# VGA.net
KiCad netlist of a schematic drawn in Altium Designer
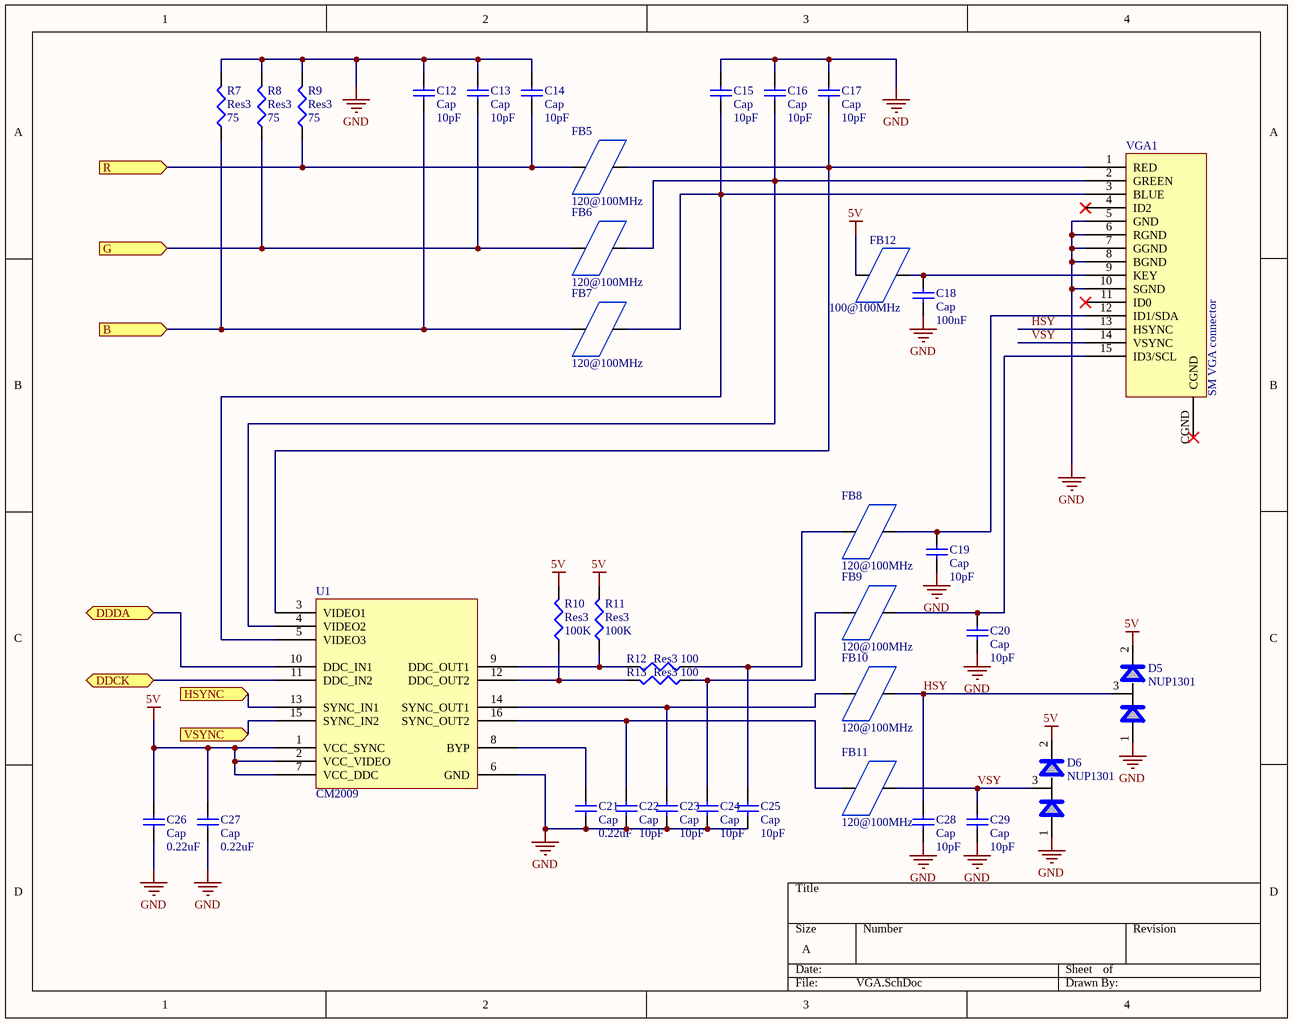
[diagram p0: VGA.SchDoc]

(export (version "E")
  (design (tool "Eeschema 10.0.6"))
  (components
    (comp (ref "C12")
      (value "Cap")
      (footprint "0603")
      (description "Capacitor")
      (fields (field (name "ALTIUM_VALUE") "10pF") (field (name "PUBLISHER") "Altium Limited"))
      (libsource (lib "Miscellaneous Devices") (part "Cap"))
    )
    (comp (ref "C13")
      (value "Cap")
      (footprint "0603")
      (description "Capacitor")
      (fields (field (name "ALTIUM_VALUE") "10pF") (field (name "PUBLISHER") "Altium Limited"))
      (libsource (lib "Miscellaneous Devices") (part "Cap"))
    )
    (comp (ref "C14")
      (value "Cap")
      (footprint "0603")
      (description "Capacitor")
      (fields (field (name "ALTIUM_VALUE") "10pF") (field (name "PUBLISHER") "Altium Limited"))
      (libsource (lib "Miscellaneous Devices") (part "Cap"))
    )
    (comp (ref "C15")
      (value "Cap")
      (footprint "0603")
      (description "Capacitor")
      (fields (field (name "ALTIUM_VALUE") "10pF") (field (name "PUBLISHER") "Altium Limited"))
      (libsource (lib "Miscellaneous Devices") (part "Cap"))
    )
    (comp (ref "C16")
      (value "Cap")
      (footprint "0603")
      (description "Capacitor")
      (fields (field (name "ALTIUM_VALUE") "10pF") (field (name "PUBLISHER") "Altium Limited"))
      (libsource (lib "Miscellaneous Devices") (part "Cap"))
    )
    (comp (ref "C17")
      (value "Cap")
      (footprint "0603")
      (description "Capacitor")
      (fields (field (name "ALTIUM_VALUE") "10pF") (field (name "PUBLISHER") "Altium Limited"))
      (libsource (lib "Miscellaneous Devices") (part "Cap"))
    )
    (comp (ref "C18")
      (value "Cap")
      (footprint "0603")
      (description "Capacitor")
      (fields (field (name "ALTIUM_VALUE") "100nF") (field (name "PUBLISHER") "Altium Limited"))
      (libsource (lib "Miscellaneous Devices") (part "Cap"))
    )
    (comp (ref "C19")
      (value "Cap")
      (footprint "0603")
      (description "Capacitor")
      (fields (field (name "ALTIUM_VALUE") "10pF") (field (name "PUBLISHER") "Altium Limited"))
      (libsource (lib "Miscellaneous Devices") (part "Cap"))
    )
    (comp (ref "C20")
      (value "Cap")
      (footprint "0603")
      (description "Capacitor")
      (fields (field (name "ALTIUM_VALUE") "10pF") (field (name "PUBLISHER") "Altium Limited"))
      (libsource (lib "Miscellaneous Devices") (part "Cap"))
    )
    (comp (ref "C21")
      (value "Cap")
      (footprint "0603")
      (description "Capacitor")
      (fields (field (name "ALTIUM_VALUE") "0.22uF") (field (name "PUBLISHER") "Altium Limited"))
      (libsource (lib "Miscellaneous Devices") (part "Cap"))
    )
    (comp (ref "C22")
      (value "Cap")
      (footprint "0603")
      (description "Capacitor")
      (fields (field (name "ALTIUM_VALUE") "10pF") (field (name "PUBLISHER") "Altium Limited"))
      (libsource (lib "Miscellaneous Devices") (part "Cap"))
    )
    (comp (ref "C23")
      (value "Cap")
      (footprint "0603")
      (description "Capacitor")
      (fields (field (name "ALTIUM_VALUE") "10pF") (field (name "PUBLISHER") "Altium Limited"))
      (libsource (lib "Miscellaneous Devices") (part "Cap"))
    )
    (comp (ref "C24")
      (value "Cap")
      (footprint "0603")
      (description "Capacitor")
      (fields (field (name "ALTIUM_VALUE") "10pF") (field (name "PUBLISHER") "Altium Limited"))
      (libsource (lib "Miscellaneous Devices") (part "Cap"))
    )
    (comp (ref "C25")
      (value "Cap")
      (footprint "0603")
      (description "Capacitor")
      (fields (field (name "ALTIUM_VALUE") "10pF") (field (name "PUBLISHER") "Altium Limited"))
      (libsource (lib "Miscellaneous Devices") (part "Cap"))
    )
    (comp (ref "C26")
      (value "Cap")
      (footprint "0603")
      (description "Capacitor")
      (fields (field (name "ALTIUM_VALUE") "0.22uF") (field (name "PUBLISHER") "Altium Limited"))
      (libsource (lib "Miscellaneous Devices") (part "Cap"))
    )
    (comp (ref "C27")
      (value "Cap")
      (footprint "0603")
      (description "Capacitor")
      (fields (field (name "ALTIUM_VALUE") "0.22uF") (field (name "PUBLISHER") "Altium Limited"))
      (libsource (lib "Miscellaneous Devices") (part "Cap"))
    )
    (comp (ref "C28")
      (value "Cap")
      (footprint "0603")
      (description "Capacitor")
      (fields (field (name "ALTIUM_VALUE") "10pF") (field (name "PUBLISHER") "Altium Limited"))
      (libsource (lib "Miscellaneous Devices") (part "Cap"))
    )
    (comp (ref "C29")
      (value "Cap")
      (footprint "0603")
      (description "Capacitor")
      (fields (field (name "ALTIUM_VALUE") "10pF") (field (name "PUBLISHER") "Altium Limited"))
      (libsource (lib "Miscellaneous Devices") (part "Cap"))
    )
    (comp (ref "D5")
      (value "NUP1301")
      (footprint "SOT23")
      (description "Low Capacitance Diode Array for ESD Protection")
      (libsource (lib "Diodes") (part "NUP1301"))
    )
    (comp (ref "D6")
      (value "NUP1301")
      (footprint "SOT23")
      (description "Low Capacitance Diode Array for ESD Protection")
      (libsource (lib "Diodes") (part "NUP1301"))
    )
    (comp (ref "FB5")
      (value "120@100MHz")
      (footprint "INDC1608X09N")
      (description "Ferrite Bead")
      (libsource (lib "BKP1608 - Ferrite Bead") (part "Ferrite Bead"))
    )
    (comp (ref "FB6")
      (value "120@100MHz")
      (footprint "INDC1608X09N")
      (description "Ferrite Bead")
      (libsource (lib "BKP1608 - Ferrite Bead") (part "Ferrite Bead"))
    )
    (comp (ref "FB7")
      (value "120@100MHz")
      (footprint "INDC1608X09N")
      (description "Ferrite Bead")
      (libsource (lib "BKP1608 - Ferrite Bead") (part "Ferrite Bead"))
    )
    (comp (ref "FB8")
      (value "120@100MHz")
      (footprint "INDC1608X09N")
      (description "Ferrite Bead")
      (libsource (lib "BKP1608 - Ferrite Bead") (part "Ferrite Bead"))
    )
    (comp (ref "FB9")
      (value "120@100MHz")
      (footprint "INDC1608X09N")
      (description "Ferrite Bead")
      (libsource (lib "BKP1608 - Ferrite Bead") (part "Ferrite Bead"))
    )
    (comp (ref "FB10")
      (value "120@100MHz")
      (footprint "INDC1608X09N")
      (description "Ferrite Bead")
      (libsource (lib "BKP1608 - Ferrite Bead") (part "Ferrite Bead"))
    )
    (comp (ref "FB11")
      (value "120@100MHz")
      (footprint "INDC1608X09N")
      (description "Ferrite Bead")
      (libsource (lib "BKP1608 - Ferrite Bead") (part "Ferrite Bead"))
    )
    (comp (ref "FB12")
      (value "100@100MHz")
      (footprint "INDC1608X09N")
      (description "Ferrite Bead")
      (libsource (lib "BKP1608 - Ferrite Bead") (part "Ferrite Bead"))
    )
    (comp (ref "R7")
      (value "Res3")
      (footprint "J1-0603")
      (description "Resistor")
      (fields (field (name "ALTIUM_VALUE") "75") (field (name "PUBLISHER") "Altium Limited"))
      (libsource (lib "Miscellaneous Devices") (part "Res3"))
    )
    (comp (ref "R8")
      (value "Res3")
      (footprint "J1-0603")
      (description "Resistor")
      (fields (field (name "ALTIUM_VALUE") "75") (field (name "PUBLISHER") "Altium Limited"))
      (libsource (lib "Miscellaneous Devices") (part "Res3"))
    )
    (comp (ref "R9")
      (value "Res3")
      (footprint "J1-0603")
      (description "Resistor")
      (fields (field (name "ALTIUM_VALUE") "75") (field (name "PUBLISHER") "Altium Limited"))
      (libsource (lib "Miscellaneous Devices") (part "Res3"))
    )
    (comp (ref "R10")
      (value "Res3")
      (footprint "J1-0603")
      (description "Resistor")
      (fields (field (name "ALTIUM_VALUE") "100K") (field (name "PUBLISHER") "Altium Limited"))
      (libsource (lib "Miscellaneous Devices") (part "Res3"))
    )
    (comp (ref "R11")
      (value "Res3")
      (footprint "J1-0603")
      (description "Resistor")
      (fields (field (name "ALTIUM_VALUE") "100K") (field (name "PUBLISHER") "Altium Limited"))
      (libsource (lib "Miscellaneous Devices") (part "Res3"))
    )
    (comp (ref "R12")
      (value "Res3")
      (footprint "J1-0603")
      (description "Resistor")
      (fields (field (name "ALTIUM_VALUE") "100") (field (name "PUBLISHER") "Altium Limited"))
      (libsource (lib "Miscellaneous Devices") (part "Res3"))
    )
    (comp (ref "R13")
      (value "Res3")
      (footprint "J1-0603")
      (description "Resistor")
      (fields (field (name "ALTIUM_VALUE") "100") (field (name "PUBLISHER") "Altium Limited"))
      (libsource (lib "Miscellaneous Devices") (part "Res3"))
    )
    (comp (ref "U1")
      (value "CM2009")
      (footprint "SOP64P630X173-16N")
      (description "VGA ESD Protection")
      (libsource (lib "CM2009") (part "CM2009"))
    )
    (comp (ref "VGA1")
      (value "SM VGA connector")
      (footprint "15POS SM 30MIL-PITCH")
      (libsource (lib "VGA_SMconnectors") (part "VGA"))
    )
  )
  (nets
    (net (code "1") (name "/B") (class "Default")
      (node (ref "C12") (pin "1") (pinfunction "1_1") (pintype "passive"))
      (node (ref "FB7") (pin "1") (pinfunction "1_1") (pintype "passive"))
      (node (ref "R7") (pin "1") (pinfunction "1_1") (pintype "passive"))
    )
    (net (code "2") (name "/DDCK") (class "Default")
      (node (ref "U1") (pin "11") (pinfunction "DDC_IN2_11") (pintype "passive"))
    )
    (net (code "3") (name "/DDDA") (class "Default")
      (node (ref "U1") (pin "10") (pinfunction "DDC_IN1_10") (pintype "passive"))
    )
    (net (code "4") (name "/G") (class "Default")
      (node (ref "C13") (pin "1") (pinfunction "1_1") (pintype "passive"))
      (node (ref "FB6") (pin "1") (pinfunction "1_1") (pintype "passive"))
      (node (ref "R8") (pin "1") (pinfunction "1_1") (pintype "passive"))
    )
    (net (code "5") (name "/HSY") (class "Default")
      (node (ref "C28") (pin "2") (pinfunction "2_2") (pintype "passive"))
      (node (ref "D5") (pin "3") (pinfunction "3_3") (pintype "passive"))
      (node (ref "FB10") (pin "2") (pinfunction "2_2") (pintype "passive"))
      (node (ref "VGA1") (pin "13") (pinfunction "HSYNC_13") (pintype "passive"))
    )
    (net (code "6") (name "/HSYNC") (class "Default")
      (node (ref "U1") (pin "13") (pinfunction "SYNC_IN1_13") (pintype "passive"))
    )
    (net (code "7") (name "/R") (class "Default")
      (node (ref "C14") (pin "1") (pinfunction "1_1") (pintype "passive"))
      (node (ref "FB5") (pin "1") (pinfunction "1_1") (pintype "passive"))
      (node (ref "R9") (pin "1") (pinfunction "1_1") (pintype "passive"))
    )
    (net (code "8") (name "/VSY") (class "Default")
      (node (ref "C29") (pin "2") (pinfunction "2_2") (pintype "passive"))
      (node (ref "D6") (pin "3") (pinfunction "3_3") (pintype "passive"))
      (node (ref "FB11") (pin "2") (pinfunction "2_2") (pintype "passive"))
      (node (ref "VGA1") (pin "14") (pinfunction "VSYNC_14") (pintype "passive"))
    )
    (net (code "9") (name "/VSYNC") (class "Default")
      (node (ref "U1") (pin "15") (pinfunction "SYNC_IN2_15") (pintype "passive"))
    )
    (net (code "10") (name "5V") (class "Default")
      (node (ref "C26") (pin "2") (pinfunction "2_2") (pintype "passive"))
      (node (ref "C27") (pin "2") (pinfunction "2_2") (pintype "passive"))
      (node (ref "D5") (pin "2") (pinfunction "2_2") (pintype "passive"))
      (node (ref "D6") (pin "2") (pinfunction "2_2") (pintype "passive"))
      (node (ref "FB12") (pin "1") (pinfunction "1_1") (pintype "passive"))
      (node (ref "R10") (pin "2") (pinfunction "2_2") (pintype "passive"))
      (node (ref "R11") (pin "2") (pinfunction "2_2") (pintype "passive"))
      (node (ref "U1") (pin "1") (pinfunction "VCC_SYNC_1") (pintype "passive"))
      (node (ref "U1") (pin "2") (pinfunction "VCC_VIDEO_2") (pintype "passive"))
      (node (ref "U1") (pin "7") (pinfunction "VCC_DDC_7") (pintype "passive"))
    )
    (net (code "11") (name "GND") (class "Default")
      (node (ref "C12") (pin "2") (pinfunction "2_2") (pintype "passive"))
      (node (ref "C13") (pin "2") (pinfunction "2_2") (pintype "passive"))
      (node (ref "C14") (pin "2") (pinfunction "2_2") (pintype "passive"))
      (node (ref "C15") (pin "2") (pinfunction "2_2") (pintype "passive"))
      (node (ref "C16") (pin "2") (pinfunction "2_2") (pintype "passive"))
      (node (ref "C17") (pin "2") (pinfunction "2_2") (pintype "passive"))
      (node (ref "C18") (pin "1") (pinfunction "1_1") (pintype "passive"))
      (node (ref "C19") (pin "1") (pinfunction "1_1") (pintype "passive"))
      (node (ref "C20") (pin "1") (pinfunction "1_1") (pintype "passive"))
      (node (ref "C21") (pin "1") (pinfunction "1_1") (pintype "passive"))
      (node (ref "C22") (pin "1") (pinfunction "1_1") (pintype "passive"))
      (node (ref "C23") (pin "1") (pinfunction "1_1") (pintype "passive"))
      (node (ref "C24") (pin "1") (pinfunction "1_1") (pintype "passive"))
      (node (ref "C25") (pin "1") (pinfunction "1_1") (pintype "passive"))
      (node (ref "C26") (pin "1") (pinfunction "1_1") (pintype "passive"))
      (node (ref "C27") (pin "1") (pinfunction "1_1") (pintype "passive"))
      (node (ref "C28") (pin "1") (pinfunction "1_1") (pintype "passive"))
      (node (ref "C29") (pin "1") (pinfunction "1_1") (pintype "passive"))
      (node (ref "D5") (pin "1") (pinfunction "1_1") (pintype "passive"))
      (node (ref "D6") (pin "1") (pinfunction "1_1") (pintype "passive"))
      (node (ref "R7") (pin "2") (pinfunction "2_2") (pintype "passive"))
      (node (ref "R8") (pin "2") (pinfunction "2_2") (pintype "passive"))
      (node (ref "R9") (pin "2") (pinfunction "2_2") (pintype "passive"))
      (node (ref "U1") (pin "6") (pinfunction "GND_6") (pintype "passive"))
      (node (ref "VGA1") (pin "10") (pinfunction "SGND_10") (pintype "passive"))
      (node (ref "VGA1") (pin "5") (pinfunction "GND_5") (pintype "passive"))
      (node (ref "VGA1") (pin "6") (pinfunction "RGND_6") (pintype "passive"))
      (node (ref "VGA1") (pin "7") (pinfunction "GGND_7") (pintype "passive"))
      (node (ref "VGA1") (pin "8") (pinfunction "BGND_8") (pintype "passive"))
    )
    (net (code "12") (name "Net-(C24-Pad2)") (class "Default")
      (node (ref "C24") (pin "2") (pinfunction "2_2") (pintype "passive"))
      (node (ref "FB9") (pin "1") (pinfunction "1_1") (pintype "passive"))
      (node (ref "R13") (pin "1") (pinfunction "1_1") (pintype "passive"))
    )
    (net (code "13") (name "Net-(C25-Pad2)") (class "Default")
      (node (ref "C25") (pin "2") (pinfunction "2_2") (pintype "passive"))
      (node (ref "FB8") (pin "1") (pinfunction "1_1") (pintype "passive"))
      (node (ref "R12") (pin "1") (pinfunction "1_1") (pintype "passive"))
    )
    (net (code "14") (name "Net-(U1-BYP)") (class "Default")
      (node (ref "C21") (pin "2") (pinfunction "2_2") (pintype "passive"))
      (node (ref "U1") (pin "8") (pinfunction "BYP_8") (pintype "passive"))
    )
    (net (code "15") (name "Net-(U1-DDC_OUT1)") (class "Default")
      (node (ref "R11") (pin "1") (pinfunction "1_1") (pintype "passive"))
      (node (ref "R12") (pin "2") (pinfunction "2_2") (pintype "passive"))
      (node (ref "U1") (pin "9") (pinfunction "DDC_OUT1_9") (pintype "passive"))
    )
    (net (code "16") (name "Net-(U1-DDC_OUT2)") (class "Default")
      (node (ref "R10") (pin "1") (pinfunction "1_1") (pintype "passive"))
      (node (ref "R13") (pin "2") (pinfunction "2_2") (pintype "passive"))
      (node (ref "U1") (pin "12") (pinfunction "DDC_OUT2_12") (pintype "passive"))
    )
    (net (code "17") (name "Net-(U1-SYNC_OUT1)") (class "Default")
      (node (ref "C23") (pin "2") (pinfunction "2_2") (pintype "passive"))
      (node (ref "FB10") (pin "1") (pinfunction "1_1") (pintype "passive"))
      (node (ref "U1") (pin "14") (pinfunction "SYNC_OUT1_14") (pintype "passive"))
    )
    (net (code "18") (name "Net-(U1-SYNC_OUT2)") (class "Default")
      (node (ref "C22") (pin "2") (pinfunction "2_2") (pintype "passive"))
      (node (ref "FB11") (pin "1") (pinfunction "1_1") (pintype "passive"))
      (node (ref "U1") (pin "16") (pinfunction "SYNC_OUT2_16") (pintype "passive"))
    )
    (net (code "19") (name "Net-(U1-VIDEO1)") (class "Default")
      (node (ref "C17") (pin "1") (pinfunction "1_1") (pintype "passive"))
      (node (ref "FB5") (pin "2") (pinfunction "2_2") (pintype "passive"))
      (node (ref "U1") (pin "3") (pinfunction "VIDEO1_3") (pintype "passive"))
      (node (ref "VGA1") (pin "1") (pinfunction "RED_1") (pintype "passive"))
    )
    (net (code "20") (name "Net-(U1-VIDEO2)") (class "Default")
      (node (ref "C16") (pin "1") (pinfunction "1_1") (pintype "passive"))
      (node (ref "FB6") (pin "2") (pinfunction "2_2") (pintype "passive"))
      (node (ref "U1") (pin "4") (pinfunction "VIDEO2_4") (pintype "passive"))
      (node (ref "VGA1") (pin "2") (pinfunction "GREEN_2") (pintype "passive"))
    )
    (net (code "21") (name "Net-(U1-VIDEO3)") (class "Default")
      (node (ref "C15") (pin "1") (pinfunction "1_1") (pintype "passive"))
      (node (ref "FB7") (pin "2") (pinfunction "2_2") (pintype "passive"))
      (node (ref "U1") (pin "5") (pinfunction "VIDEO3_5") (pintype "passive"))
      (node (ref "VGA1") (pin "3") (pinfunction "BLUE_3") (pintype "passive"))
    )
    (net (code "22") (name "Net-(VGA1-ID1{slash}SDA)") (class "Default")
      (node (ref "C19") (pin "2") (pinfunction "2_2") (pintype "passive"))
      (node (ref "FB8") (pin "2") (pinfunction "2_2") (pintype "passive"))
      (node (ref "VGA1") (pin "12") (pinfunction "ID1/SDA_12") (pintype "passive"))
    )
    (net (code "23") (name "Net-(VGA1-ID3{slash}SCL)") (class "Default")
      (node (ref "C20") (pin "2") (pinfunction "2_2") (pintype "passive"))
      (node (ref "FB9") (pin "2") (pinfunction "2_2") (pintype "passive"))
      (node (ref "VGA1") (pin "15") (pinfunction "ID3/SCL_15") (pintype "passive"))
    )
    (net (code "24") (name "Net-(VGA1-KEY)") (class "Default")
      (node (ref "C18") (pin "2") (pinfunction "2_2") (pintype "passive"))
      (node (ref "FB12") (pin "2") (pinfunction "2_2") (pintype "passive"))
      (node (ref "VGA1") (pin "9") (pinfunction "KEY_9") (pintype "passive"))
    )
    (net (code "25") (name "unconnected-(VGA1-ID0-Pad11)") (class "Default")
      (node (ref "VGA1") (pin "11") (pinfunction "ID0_11") (pintype "passive+no_connect"))
    )
    (net (code "26") (name "unconnected-(VGA1-ID2-Pad4)") (class "Default")
      (node (ref "VGA1") (pin "4") (pinfunction "ID2_4") (pintype "passive+no_connect"))
    )
    (net (code "27") (name "unconnected-(VGA1-PadCGND)") (class "Default")
      (node (ref "VGA1") (pin "CGND") (pinfunction "CGND_CGND") (pintype "passive+no_connect"))
    )
  )
)
